# RLC_PCB.net
KiCad netlist of a schematic drawn in EasyEDA
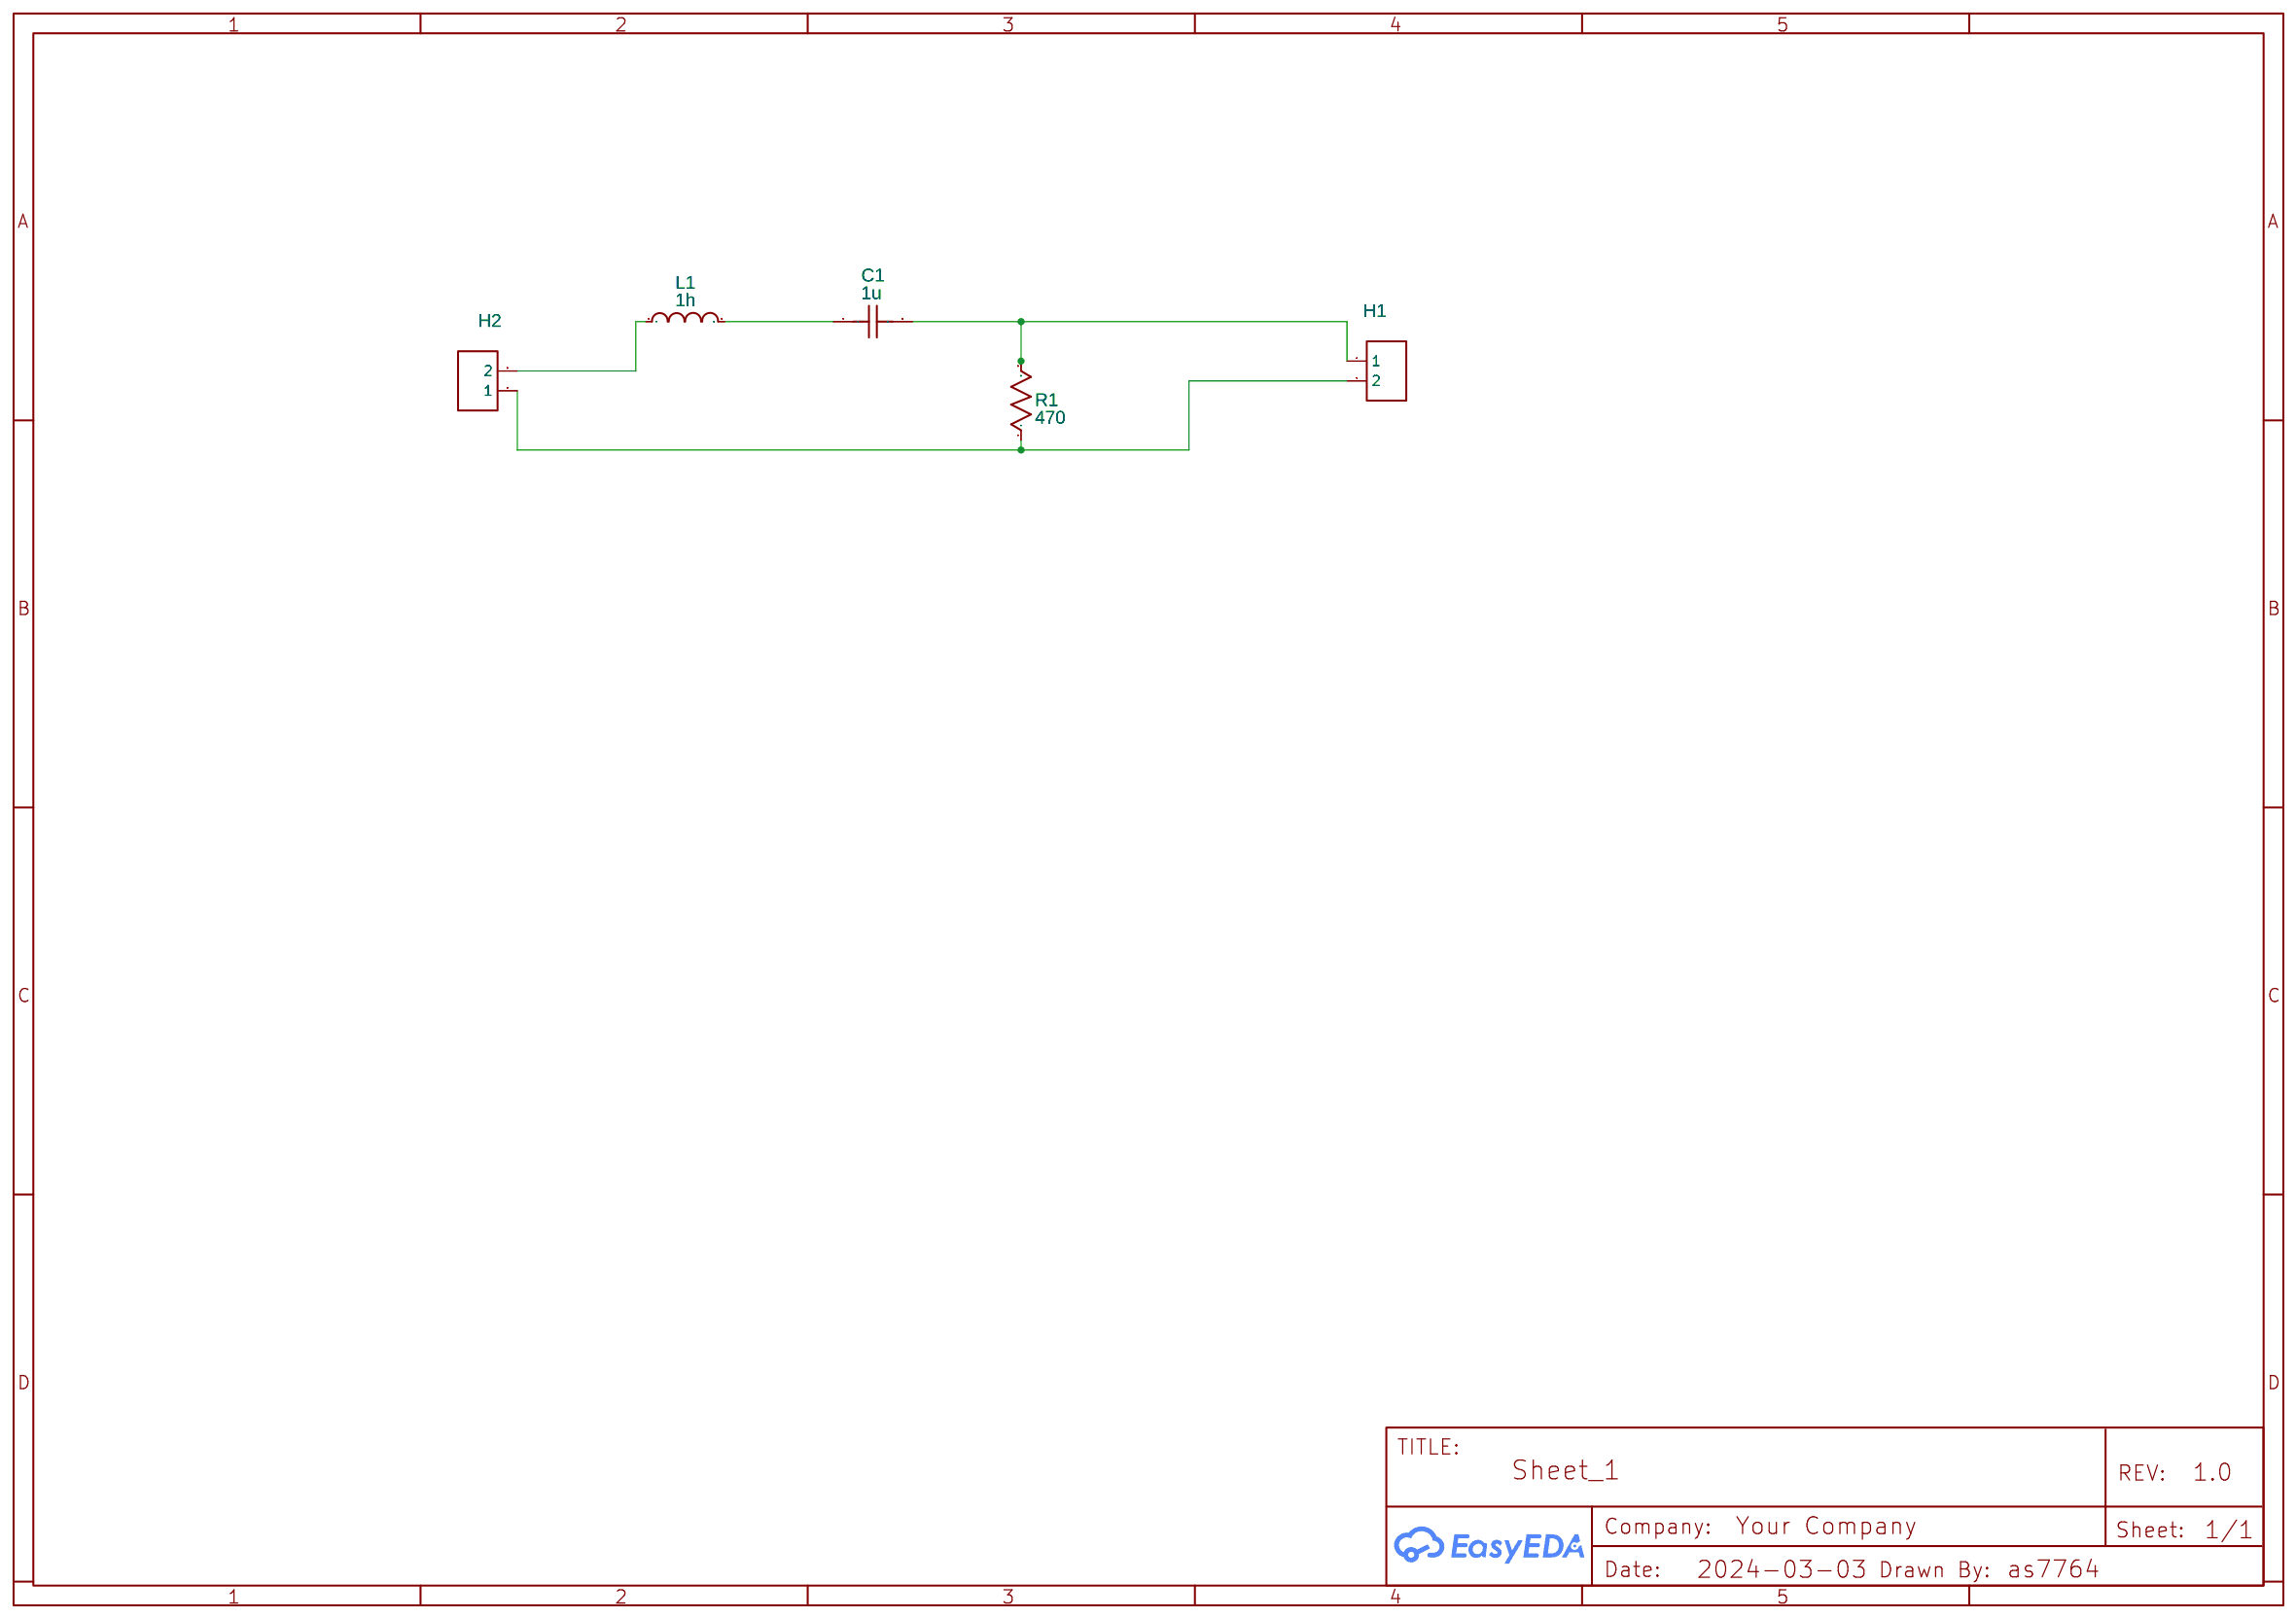
[diagram p0: schematic sheet]

(export (version "E")
  (design (tool "Eeschema 10.0.6"))
  (components
    (comp (ref "C1") (value "1u") (libsource (lib "") (part "C_RAD-0.1_US")))
    (comp (ref "H1") (value "HDR-F-2.54_1x2") (libsource (lib "") (part "HDR-F-2.54_1x2_1")))
    (comp (ref "H2") (value "HDR-F-2.54_1x2") (libsource (lib "") (part "HDR-F-2.54_1x2")))
    (comp (ref "L1") (value "1h") (libsource (lib "") (part "L_AXIAL-0.4_US")))
    (comp (ref "R1") (value "470") (libsource (lib "") (part "R_AXIAL-0.3_US")))
  )
  (nets
    (net (code "1") (name "Net-(C1-Pad1)") (class "Default")
      (node (ref "C1") (pin "1") (pinfunction "1_1") (pintype "unspecified"))
      (node (ref "L1") (pin "2") (pinfunction "2_2") (pintype "unspecified"))
    )
    (net (code "2") (name "Net-(C1-Pad2)") (class "Default")
      (node (ref "C1") (pin "2") (pinfunction "2_2") (pintype "unspecified"))
      (node (ref "H1") (pin "1") (pinfunction "1_1") (pintype "input"))
      (node (ref "R1") (pin "2") (pinfunction "2_2") (pintype "unspecified"))
    )
    (net (code "3") (name "Net-(H1-Pad2)") (class "Default")
      (node (ref "H1") (pin "2") (pinfunction "2_2") (pintype "input"))
      (node (ref "H2") (pin "1") (pinfunction "1_1") (pintype "input"))
      (node (ref "R1") (pin "1") (pinfunction "1_1") (pintype "unspecified"))
    )
    (net (code "4") (name "Net-(H2-Pad2)") (class "Default")
      (node (ref "H2") (pin "2") (pinfunction "2_2") (pintype "input"))
      (node (ref "L1") (pin "1") (pinfunction "1_1") (pintype "unspecified"))
    )
  )
)
